# DAC.net
KiCad netlist of a schematic drawn in Altium Designer
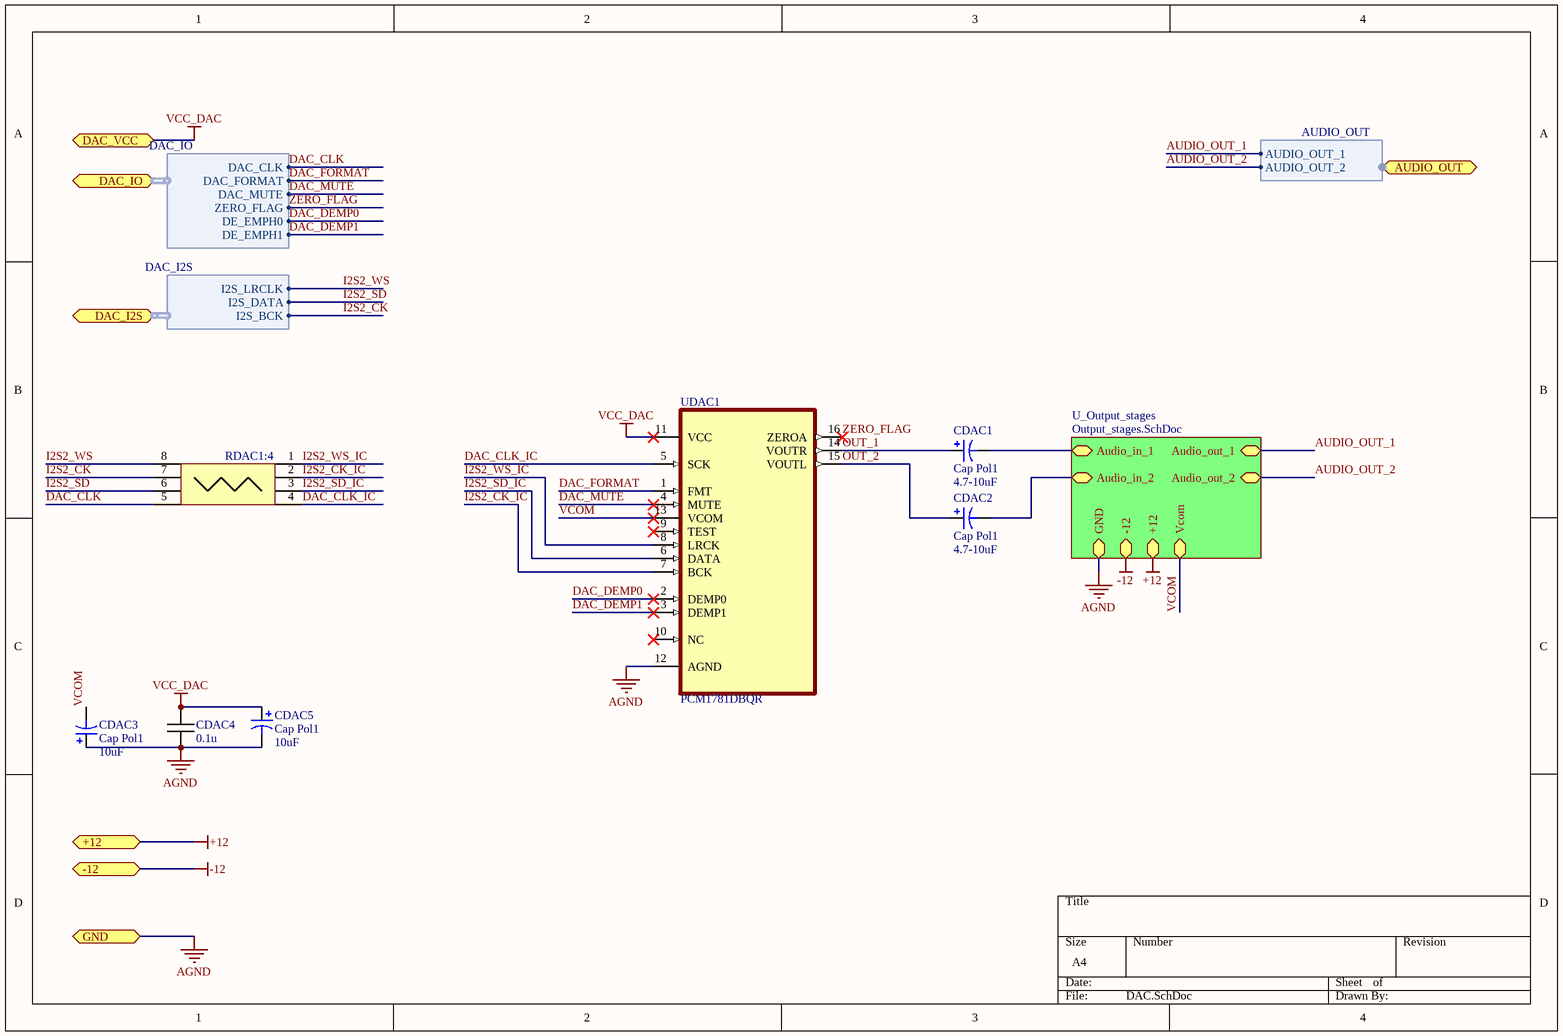
[diagram p0: DAC.SchDoc]

(export (version "E")
  (design (tool "Eeschema 10.0.6"))
  (components
    (comp (ref "CDAC1")
      (value "Cap Pol1")
      (footprint "C-RAD-4.5")
      (description "Polarized Capacitor (Radial)")
      (fields (field (name "ALTIUM_VALUE") "4.7-10uF") (field (name "PUBLISHER") "Altium Limited"))
      (libsource (lib "Miscellaneous Devices") (part "Cap Pol1"))
    )
    (comp (ref "CDAC2")
      (value "Cap Pol1")
      (footprint "C-RAD-4.5")
      (description "Polarized Capacitor (Radial)")
      (fields (field (name "ALTIUM_VALUE") "4.7-10uF") (field (name "PUBLISHER") "Altium Limited"))
      (libsource (lib "Miscellaneous Devices") (part "Cap Pol1"))
    )
    (comp (ref "CDAC3")
      (value "Cap Pol1")
      (footprint "C-RAD-4.5")
      (description "Polarized Capacitor (Radial)")
      (fields (field (name "ALTIUM_VALUE") "10uF") (field (name "PUBLISHER") "Altium Limited"))
      (libsource (lib "Miscellaneous Devices") (part "Cap Pol1"))
    )
    (comp (ref "CDAC4")
      (value "0.1u")
      (footprint "C 0603 / 1608")
      (libsource (lib "Standard") (part "Capacitor"))
    )
    (comp (ref "CDAC5")
      (value "Cap Pol1")
      (footprint "C-RAD-4.5")
      (description "Polarized Capacitor (Radial)")
      (fields (field (name "ALTIUM_VALUE") "10uF") (field (name "PUBLISHER") "Altium Limited"))
      (libsource (lib "Miscellaneous Devices") (part "Cap Pol1"))
    )
    (comp (ref "RDAC1:4")
      (value "742C083121JP")
      (footprint "RESARRAY(4x0603)")
      (fields (field (name "MF") "CTS Resistor"))
      (libsource (lib "Standard") (part "Resistor Array 4x"))
    )
    (comp (ref "UDAC1")
      (value "PCM1781DBQR")
      (footprint "SOP16-63P600X175-16N")
      (description "Converters - Digital to Analog _DAC_ 24-Bit, 192kHz, Ster Delta-Sig Audio DAC")
      (fields (field (name "MF") "Texas Instruments"))
      (libsource (lib "IC") (part "PCM1781DBQR"))
    )
  )
  (nets
    (net (code "8") (name "/Audio_in_1") (class "Default")
      (node (ref "CDAC1") (pin "2") (pinfunction "2_2") (pintype "passive"))
    )
    (net (code "9") (name "/Audio_in_2") (class "Default")
      (node (ref "CDAC2") (pin "2") (pinfunction "2_2") (pintype "passive"))
    )
    (net (code "10") (name "/DAC_CLK") (class "Default")
      (node (ref "RDAC1:4") (pin "5") (pinfunction "5_5") (pintype "passive"))
    )
    (net (code "11") (name "/DAC_CLK_IC") (class "Default")
      (node (ref "RDAC1:4") (pin "4") (pinfunction "4_4") (pintype "passive"))
      (node (ref "UDAC1") (pin "5") (pinfunction "SCK_5") (pintype "input"))
    )
    (net (code "12") (name "/DAC_DEMP0") (class "Default")
      (node (ref "UDAC1") (pin "2") (pinfunction "DEMP0_2") (pintype "input+no_connect"))
    )
    (net (code "13") (name "/DAC_DEMP1") (class "Default")
      (node (ref "UDAC1") (pin "3") (pinfunction "DEMP1_3") (pintype "input"))
    )
    (net (code "14") (name "/DAC_FORMAT") (class "Default")
      (node (ref "UDAC1") (pin "1") (pinfunction "FMT_1") (pintype "input"))
    )
    (net (code "15") (name "/DAC_MUTE") (class "Default")
      (node (ref "UDAC1") (pin "4") (pinfunction "MUTE_4") (pintype "input+no_connect"))
    )
    (net (code "16") (name "/I2S2_CK") (class "Default")
      (node (ref "RDAC1:4") (pin "7") (pinfunction "7_7") (pintype "passive"))
    )
    (net (code "17") (name "/I2S2_CK_IC") (class "Default")
      (node (ref "RDAC1:4") (pin "2") (pinfunction "2_2") (pintype "passive"))
      (node (ref "UDAC1") (pin "7") (pinfunction "BCK_7") (pintype "input"))
    )
    (net (code "18") (name "/I2S2_SD") (class "Default")
      (node (ref "RDAC1:4") (pin "6") (pinfunction "6_6") (pintype "passive"))
    )
    (net (code "19") (name "/I2S2_SD_IC") (class "Default")
      (node (ref "RDAC1:4") (pin "3") (pinfunction "3_3") (pintype "passive"))
      (node (ref "UDAC1") (pin "6") (pinfunction "DATA_6") (pintype "input"))
    )
    (net (code "20") (name "/I2S2_WS") (class "Default")
      (node (ref "RDAC1:4") (pin "8") (pinfunction "8_8") (pintype "passive"))
    )
    (net (code "21") (name "/I2S2_WS_IC") (class "Default")
      (node (ref "RDAC1:4") (pin "1") (pinfunction "1_1") (pintype "passive"))
      (node (ref "UDAC1") (pin "8") (pinfunction "LRCK_8") (pintype "input"))
    )
    (net (code "22") (name "/OUT_1") (class "Default")
      (node (ref "CDAC1") (pin "1") (pinfunction "1_1") (pintype "passive"))
      (node (ref "UDAC1") (pin "14") (pinfunction "VOUTR_14") (pintype "output"))
    )
    (net (code "23") (name "/OUT_2") (class "Default")
      (node (ref "CDAC2") (pin "1") (pinfunction "1_1") (pintype "passive"))
      (node (ref "UDAC1") (pin "15") (pinfunction "VOUTL_15") (pintype "output"))
    )
    (net (code "24") (name "/VCOM") (class "Default")
      (node (ref "CDAC3") (pin "2") (pinfunction "2_2") (pintype "passive"))
      (node (ref "UDAC1") (pin "13") (pinfunction "VCOM_13") (pintype "passive"))
    )
    (net (code "25") (name "/ZERO_FLAG") (class "Default")
      (node (ref "UDAC1") (pin "16") (pinfunction "ZEROA_16") (pintype "output+no_connect"))
    )
    (net (code "29") (name "AGND") (class "Default")
      (node (ref "CDAC3") (pin "1") (pinfunction "1_1") (pintype "passive"))
      (node (ref "CDAC4") (pin "2") (pinfunction "1_2") (pintype "passive"))
      (node (ref "CDAC5") (pin "2") (pinfunction "2_2") (pintype "passive"))
      (node (ref "UDAC1") (pin "12") (pinfunction "AGND_12") (pintype "passive"))
    )
    (net (code "30") (name "VCC_DAC") (class "Default")
      (node (ref "CDAC4") (pin "1") (pinfunction "1_1") (pintype "passive"))
      (node (ref "CDAC5") (pin "1") (pinfunction "1_1") (pintype "passive"))
      (node (ref "UDAC1") (pin "11") (pinfunction "VCC_11") (pintype "power_in"))
    )
    (net (code "31") (name "unconnected-(UDAC1-NC-Pad10)") (class "Default")
      (node (ref "UDAC1") (pin "10") (pinfunction "NC_10") (pintype "input+no_connect"))
    )
    (net (code "32") (name "unconnected-(UDAC1-TEST-Pad9)") (class "Default")
      (node (ref "UDAC1") (pin "9") (pinfunction "TEST_9") (pintype "input+no_connect"))
    )
  )
)
